# Cargador_RasPi3HAT_CamSlot_v1_0.net
KiCad netlist of a schematic drawn in EAGLE
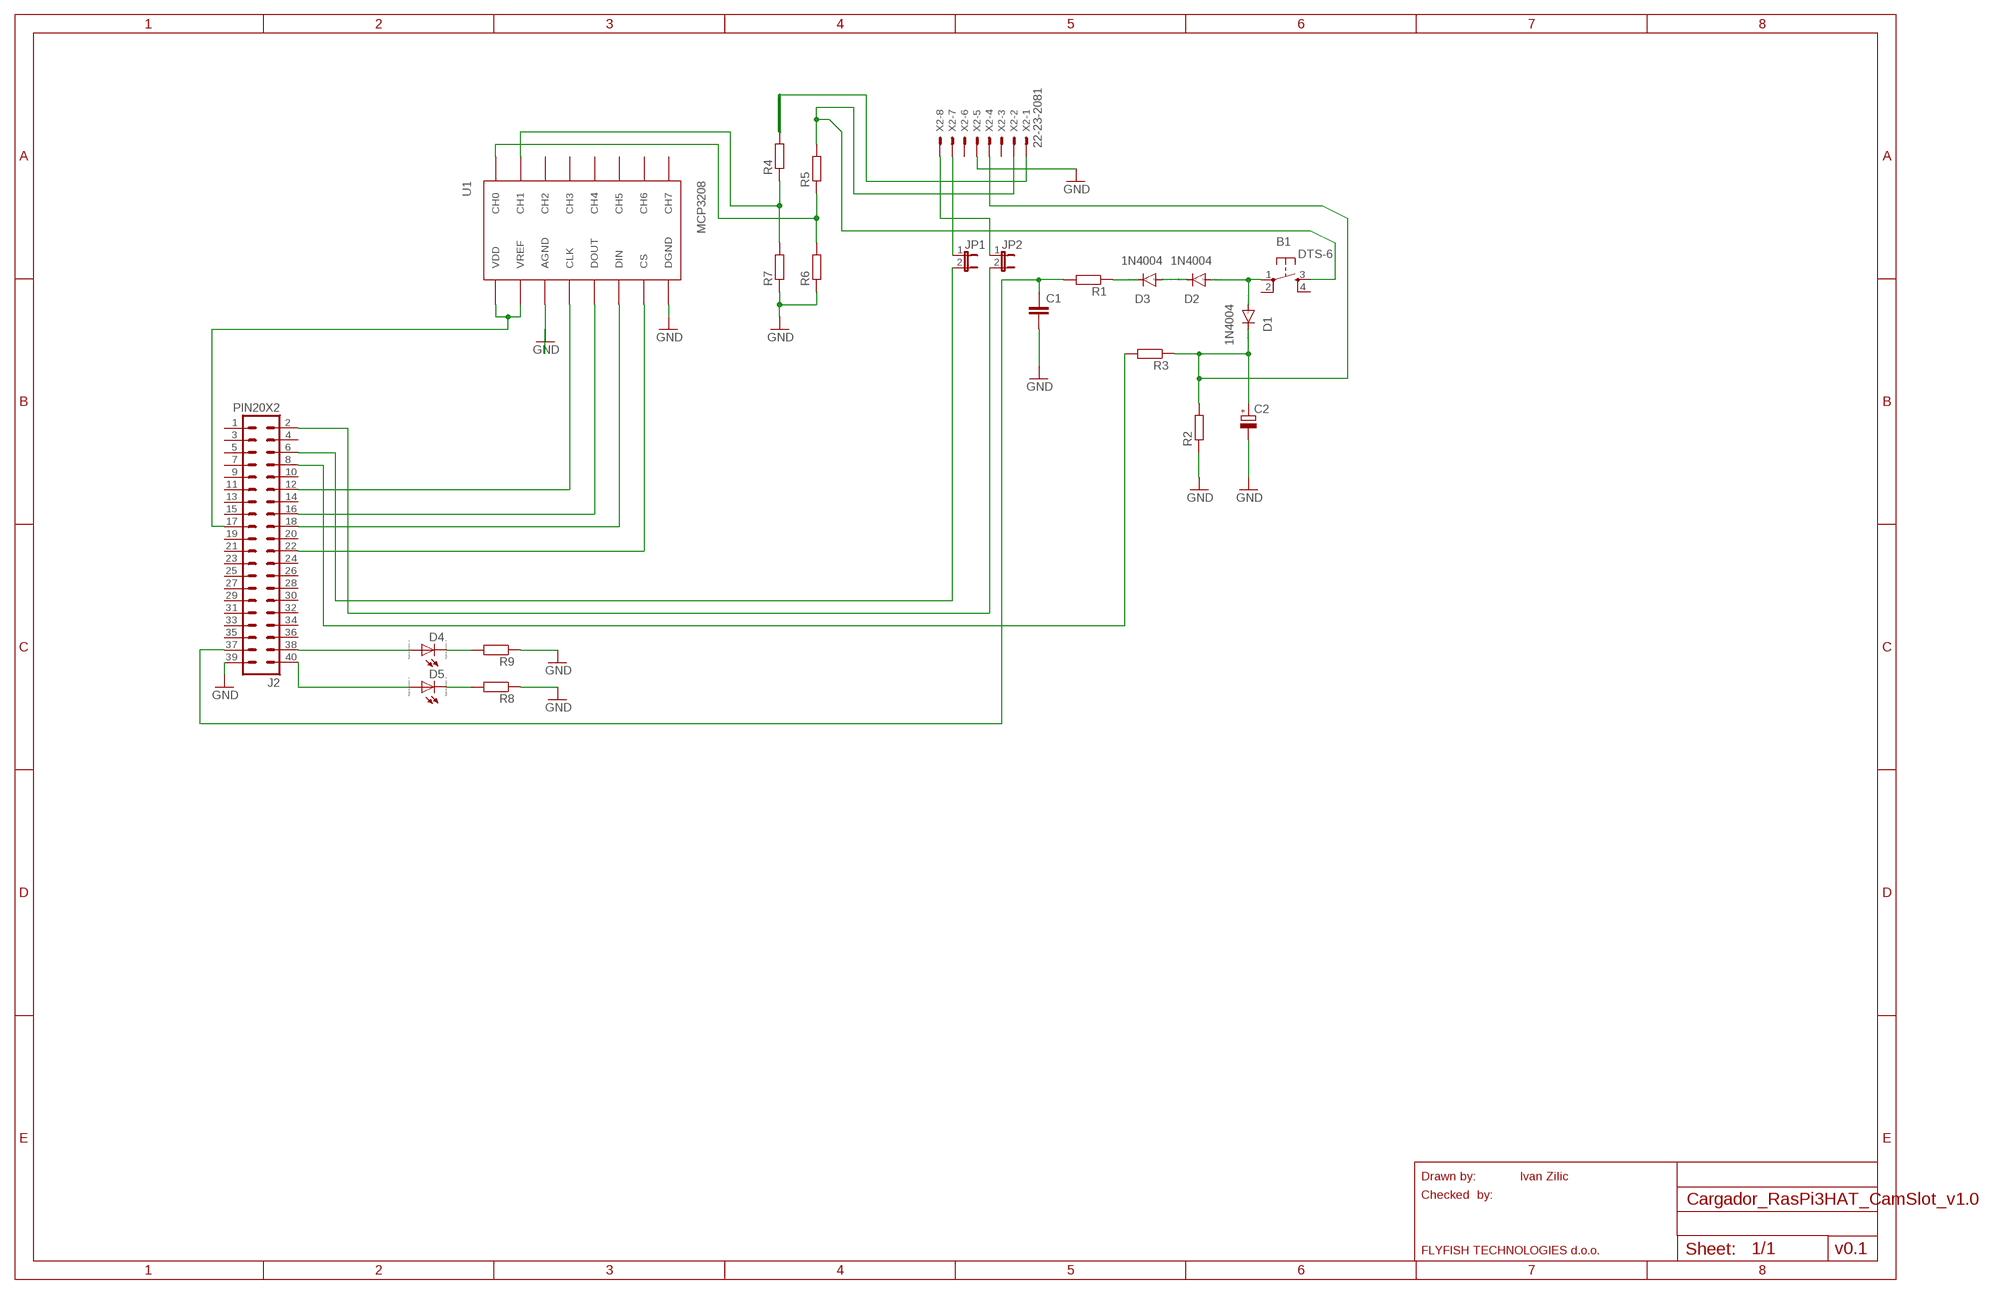
[diagram p0: schematic, sheet 1]

(export (version "E")
  (design (tool "Eeschema 10.0.6"))
  (components
    (comp (ref "B1")
      (value "DTS-6")
      (footprint "eagle-import:DTS-6")
      (libsource (lib "eagle-import") (part "DTS-6"))
    )
    (comp (ref "C1")
      (value "C2.5/2")
      (footprint "eagle-import:C2.5-2")
      (libsource (lib "eagle-import") (part "C2.5/2"))
    )
    (comp (ref "C2")
      (value "CPOL-EUE5-4")
      (footprint "eagle-import:E5-4")
      (libsource (lib "eagle-import") (part "CPOL-EUE5-4"))
    )
    (comp (ref "D1")
      (value "1N4004")
      (footprint "eagle-import:DO41-10")
      (libsource (lib "eagle-import") (part "1N4004"))
    )
    (comp (ref "D2")
      (value "1N4004")
      (footprint "eagle-import:DO41-10")
      (libsource (lib "eagle-import") (part "1N4004"))
    )
    (comp (ref "D3")
      (value "1N4004")
      (footprint "eagle-import:DO41-10")
      (libsource (lib "eagle-import") (part "1N4004"))
    )
    (comp (ref "D4")
      (value "LED_ELD260")
      (footprint "eagle-import:LED_LD260")
      (libsource (lib "eagle-import") (part "LED_ELD260"))
    )
    (comp (ref "D5")
      (value "LED_ELD260")
      (footprint "eagle-import:LED_LD260")
      (libsource (lib "eagle-import") (part "LED_ELD260"))
    )
    (comp (ref "J2")
      (value "PIN20X2")
      (footprint "eagle-import:PIN_20X2")
      (libsource (lib "eagle-import") (part "PIN20X2"))
    )
    (comp (ref "JP1")
      (value "JP1E")
      (footprint "eagle-import:JP1")
      (libsource (lib "eagle-import") (part "JP1E"))
    )
    (comp (ref "JP2")
      (value "JP1E")
      (footprint "eagle-import:JP1")
      (libsource (lib "eagle-import") (part "JP1E"))
    )
    (comp (ref "R1")
      (value "R-EU_0207/10")
      (footprint "eagle-import:0207_10")
      (libsource (lib "eagle-import") (part "R-EU_0207/10"))
    )
    (comp (ref "R2")
      (value "R-EU_0207/10")
      (footprint "eagle-import:0207_10")
      (libsource (lib "eagle-import") (part "R-EU_0207/10"))
    )
    (comp (ref "R3")
      (value "R-EU_0207/10")
      (footprint "eagle-import:0207_10")
      (libsource (lib "eagle-import") (part "R-EU_0207/10"))
    )
    (comp (ref "R4")
      (value "R-EU_0207/10")
      (footprint "eagle-import:0207_10")
      (libsource (lib "eagle-import") (part "R-EU_0207/10"))
    )
    (comp (ref "R5")
      (value "R-EU_0207/10")
      (footprint "eagle-import:0207_10")
      (libsource (lib "eagle-import") (part "R-EU_0207/10"))
    )
    (comp (ref "R6")
      (value "R-EU_0207/10")
      (footprint "eagle-import:0207_10")
      (libsource (lib "eagle-import") (part "R-EU_0207/10"))
    )
    (comp (ref "R7")
      (value "R-EU_0207/10")
      (footprint "eagle-import:0207_10")
      (libsource (lib "eagle-import") (part "R-EU_0207/10"))
    )
    (comp (ref "R8")
      (value "R-EU_0207/10")
      (footprint "eagle-import:0207_10")
      (libsource (lib "eagle-import") (part "R-EU_0207/10"))
    )
    (comp (ref "R9")
      (value "R-EU_0207/10")
      (footprint "eagle-import:0207_10")
      (libsource (lib "eagle-import") (part "R-EU_0207/10"))
    )
    (comp (ref "U1")
      (value "MCP3208")
      (footprint "eagle-import:DIL16")
      (libsource (lib "eagle-import") (part "MCP3208"))
    )
    (comp (ref "X2")
      (value "22-23-2081")
      (footprint "eagle-import:22-23-2081")
      (fields (field (name "MF") "MOLEX"))
      (libsource (lib "eagle-import") (part "22-23-2081"))
    )
  )
  (nets
    (net (code "1") (name "GND") (class "Default")
      (node (ref "C1") (pin "2") (pinfunction "2_2") (pintype "passive"))
      (node (ref "C2") (pin "-") (pinfunction "-_-") (pintype "passive"))
      (node (ref "J2") (pin "39") (pinfunction "39_39") (pintype "passive"))
      (node (ref "R2") (pin "1") (pinfunction "1_1") (pintype "passive"))
      (node (ref "R6") (pin "1") (pinfunction "1_1") (pintype "passive"))
      (node (ref "R7") (pin "1") (pinfunction "1_1") (pintype "passive"))
      (node (ref "R8") (pin "1") (pinfunction "1_1") (pintype "passive"))
      (node (ref "R9") (pin "1") (pinfunction "1_1") (pintype "passive"))
      (node (ref "U1") (pin "AGND") (pinfunction "AGND_AGND") (pintype "power_in"))
      (node (ref "U1") (pin "DGND") (pinfunction "DGND_DGND") (pintype "power_in"))
      (node (ref "X2") (pin "5") (pinfunction "S_5") (pintype "passive"))
    )
    (net (code "2") (name "Net-(B1-Pad1)") (class "Default")
      (node (ref "B1") (pin "1") (pinfunction "1_1") (pintype "passive"))
      (node (ref "D1") (pin "A") (pinfunction "A_A") (pintype "passive"))
      (node (ref "D2") (pin "A") (pinfunction "A_A") (pintype "passive"))
    )
    (net (code "3") (name "Net-(C1-Pad1)") (class "Default")
      (node (ref "C1") (pin "1") (pinfunction "1_1") (pintype "passive"))
      (node (ref "J2") (pin "37") (pinfunction "37_37") (pintype "passive"))
      (node (ref "R1") (pin "2") (pinfunction "2_2") (pintype "passive"))
    )
    (net (code "4") (name "Net-(D2-PadC)") (class "Default")
      (node (ref "D2") (pin "C") (pinfunction "C_C") (pintype "passive"))
      (node (ref "D3") (pin "A") (pinfunction "A_A") (pintype "passive"))
    )
    (net (code "5") (name "Net-(D3-PadC)") (class "Default")
      (node (ref "D3") (pin "C") (pinfunction "C_C") (pintype "passive"))
      (node (ref "R1") (pin "1") (pinfunction "1_1") (pintype "passive"))
    )
    (net (code "6") (name "Net-(D4-C)") (class "Default")
      (node (ref "D4") (pin "K") (pinfunction "C_K") (pintype "passive"))
      (node (ref "R9") (pin "2") (pinfunction "2_2") (pintype "passive"))
    )
    (net (code "7") (name "Net-(D4-PadA)") (class "Default")
      (node (ref "D4") (pin "A") (pinfunction "A_A") (pintype "passive"))
      (node (ref "J2") (pin "38") (pinfunction "38_38") (pintype "passive"))
    )
    (net (code "8") (name "Net-(D5-C)") (class "Default")
      (node (ref "D5") (pin "K") (pinfunction "C_K") (pintype "passive"))
      (node (ref "R8") (pin "2") (pinfunction "2_2") (pintype "passive"))
    )
    (net (code "9") (name "Net-(D5-PadA)") (class "Default")
      (node (ref "D5") (pin "A") (pinfunction "A_A") (pintype "passive"))
      (node (ref "J2") (pin "40") (pinfunction "40_40") (pintype "passive"))
    )
    (net (code "10") (name "Net-(J2-Pad2)") (class "Default")
      (node (ref "J2") (pin "2") (pinfunction "2_2") (pintype "passive"))
      (node (ref "JP2") (pin "2") (pinfunction "2_2") (pintype "passive"))
    )
    (net (code "11") (name "Net-(J2-Pad6)") (class "Default")
      (node (ref "J2") (pin "6") (pinfunction "6_6") (pintype "passive"))
      (node (ref "JP1") (pin "2") (pinfunction "2_2") (pintype "passive"))
    )
    (net (code "12") (name "Net-(J2-Pad8)") (class "Default")
      (node (ref "J2") (pin "8") (pinfunction "8_8") (pintype "passive"))
      (node (ref "R3") (pin "2") (pinfunction "2_2") (pintype "passive"))
    )
    (net (code "13") (name "Net-(J2-Pad12)") (class "Default")
      (node (ref "J2") (pin "12") (pinfunction "12_12") (pintype "passive"))
      (node (ref "U1") (pin "CLK") (pinfunction "CLK_CLK") (pintype "input"))
    )
    (net (code "14") (name "Net-(J2-Pad16)") (class "Default")
      (node (ref "J2") (pin "16") (pinfunction "16_16") (pintype "passive"))
      (node (ref "U1") (pin "DOUT") (pinfunction "DOUT_DOUT") (pintype "output"))
    )
    (net (code "15") (name "Net-(J2-Pad17)") (class "Default")
      (node (ref "J2") (pin "17") (pinfunction "17_17") (pintype "passive"))
      (node (ref "U1") (pin "VDD") (pinfunction "VDD_VDD") (pintype "power_in"))
      (node (ref "U1") (pin "VREF") (pinfunction "VREF_VREF") (pintype "input"))
    )
    (net (code "16") (name "Net-(J2-Pad18)") (class "Default")
      (node (ref "J2") (pin "18") (pinfunction "18_18") (pintype "passive"))
      (node (ref "U1") (pin "DIN") (pinfunction "DIN_DIN") (pintype "input"))
    )
    (net (code "17") (name "Net-(J2-Pad22)") (class "Default")
      (node (ref "J2") (pin "22") (pinfunction "22_22") (pintype "passive"))
      (node (ref "U1") (pin "CS") (pinfunction "CS_CS") (pintype "input"))
    )
    (net (code "18") (name "Net-(R4-Pad1)") (class "Default")
      (node (ref "R4") (pin "1") (pinfunction "1_1") (pintype "passive"))
      (node (ref "R7") (pin "2") (pinfunction "2_2") (pintype "passive"))
      (node (ref "U1") (pin "CH1") (pinfunction "CH1_CH1") (pintype "input"))
    )
    (net (code "19") (name "Net-(R5-Pad1)") (class "Default")
      (node (ref "R5") (pin "1") (pinfunction "1_1") (pintype "passive"))
      (node (ref "R6") (pin "2") (pinfunction "2_2") (pintype "passive"))
      (node (ref "U1") (pin "CH0") (pinfunction "CH0_CH0") (pintype "input"))
    )
    (net (code "20") (name "Net-(X2A-S)") (class "Default")
      (node (ref "R4") (pin "2") (pinfunction "2_2") (pintype "passive"))
      (node (ref "X2") (pin "1") (pinfunction "S_1") (pintype "passive"))
    )
    (net (code "21") (name "Net-(X2B-S)") (class "Default")
      (node (ref "B1") (pin "3") (pinfunction "3_3") (pintype "passive"))
      (node (ref "R5") (pin "2") (pinfunction "2_2") (pintype "passive"))
      (node (ref "X2") (pin "2") (pinfunction "S_2") (pintype "passive"))
    )
    (net (code "22") (name "Net-(X2D-S)") (class "Default")
      (node (ref "C2") (pin "+") (pinfunction "+_+") (pintype "passive"))
      (node (ref "D1") (pin "C") (pinfunction "C_C") (pintype "passive"))
      (node (ref "R2") (pin "2") (pinfunction "2_2") (pintype "passive"))
      (node (ref "R3") (pin "1") (pinfunction "1_1") (pintype "passive"))
      (node (ref "X2") (pin "4") (pinfunction "S_4") (pintype "passive"))
    )
    (net (code "23") (name "Net-(X2G-S)") (class "Default")
      (node (ref "JP1") (pin "1") (pinfunction "1_1") (pintype "passive"))
      (node (ref "X2") (pin "7") (pinfunction "S_7") (pintype "passive"))
    )
    (net (code "24") (name "Net-(X2H-S)") (class "Default")
      (node (ref "JP2") (pin "1") (pinfunction "1_1") (pintype "passive"))
      (node (ref "X2") (pin "8") (pinfunction "S_8") (pintype "passive"))
    )
    (net (code "25") (name "unconnected-(B1-Pad2)") (class "Default")
      (node (ref "B1") (pin "2") (pinfunction "2_2") (pintype "passive"))
    )
    (net (code "26") (name "unconnected-(B1-Pad4)") (class "Default")
      (node (ref "B1") (pin "4") (pinfunction "4_4") (pintype "passive"))
    )
    (net (code "27") (name "unconnected-(J2-Pad1)") (class "Default")
      (node (ref "J2") (pin "1") (pinfunction "1_1") (pintype "passive"))
    )
    (net (code "28") (name "unconnected-(J2-Pad3)") (class "Default")
      (node (ref "J2") (pin "3") (pinfunction "3_3") (pintype "passive"))
    )
    (net (code "29") (name "unconnected-(J2-Pad4)") (class "Default")
      (node (ref "J2") (pin "4") (pinfunction "4_4") (pintype "passive"))
    )
    (net (code "30") (name "unconnected-(J2-Pad5)") (class "Default")
      (node (ref "J2") (pin "5") (pinfunction "5_5") (pintype "passive"))
    )
    (net (code "31") (name "unconnected-(J2-Pad7)") (class "Default")
      (node (ref "J2") (pin "7") (pinfunction "7_7") (pintype "passive"))
    )
    (net (code "32") (name "unconnected-(J2-Pad9)") (class "Default")
      (node (ref "J2") (pin "9") (pinfunction "9_9") (pintype "passive"))
    )
    (net (code "33") (name "unconnected-(J2-Pad10)") (class "Default")
      (node (ref "J2") (pin "10") (pinfunction "10_10") (pintype "passive"))
    )
    (net (code "34") (name "unconnected-(J2-Pad11)") (class "Default")
      (node (ref "J2") (pin "11") (pinfunction "11_11") (pintype "passive"))
    )
    (net (code "35") (name "unconnected-(J2-Pad13)") (class "Default")
      (node (ref "J2") (pin "13") (pinfunction "13_13") (pintype "passive"))
    )
    (net (code "36") (name "unconnected-(J2-Pad14)") (class "Default")
      (node (ref "J2") (pin "14") (pinfunction "14_14") (pintype "passive"))
    )
    (net (code "37") (name "unconnected-(J2-Pad15)") (class "Default")
      (node (ref "J2") (pin "15") (pinfunction "15_15") (pintype "passive"))
    )
    (net (code "38") (name "unconnected-(J2-Pad19)") (class "Default")
      (node (ref "J2") (pin "19") (pinfunction "19_19") (pintype "passive"))
    )
    (net (code "39") (name "unconnected-(J2-Pad20)") (class "Default")
      (node (ref "J2") (pin "20") (pinfunction "20_20") (pintype "passive"))
    )
    (net (code "40") (name "unconnected-(J2-Pad21)") (class "Default")
      (node (ref "J2") (pin "21") (pinfunction "21_21") (pintype "passive"))
    )
    (net (code "41") (name "unconnected-(J2-Pad23)") (class "Default")
      (node (ref "J2") (pin "23") (pinfunction "23_23") (pintype "passive"))
    )
    (net (code "42") (name "unconnected-(J2-Pad24)") (class "Default")
      (node (ref "J2") (pin "24") (pinfunction "24_24") (pintype "passive"))
    )
    (net (code "43") (name "unconnected-(J2-Pad25)") (class "Default")
      (node (ref "J2") (pin "25") (pinfunction "25_25") (pintype "passive"))
    )
    (net (code "44") (name "unconnected-(J2-Pad26)") (class "Default")
      (node (ref "J2") (pin "26") (pinfunction "26_26") (pintype "passive"))
    )
    (net (code "45") (name "unconnected-(J2-Pad27)") (class "Default")
      (node (ref "J2") (pin "27") (pinfunction "27_27") (pintype "passive"))
    )
    (net (code "46") (name "unconnected-(J2-Pad28)") (class "Default")
      (node (ref "J2") (pin "28") (pinfunction "28_28") (pintype "passive"))
    )
    (net (code "47") (name "unconnected-(J2-Pad29)") (class "Default")
      (node (ref "J2") (pin "29") (pinfunction "29_29") (pintype "passive"))
    )
    (net (code "48") (name "unconnected-(J2-Pad30)") (class "Default")
      (node (ref "J2") (pin "30") (pinfunction "30_30") (pintype "passive"))
    )
    (net (code "49") (name "unconnected-(J2-Pad31)") (class "Default")
      (node (ref "J2") (pin "31") (pinfunction "31_31") (pintype "passive"))
    )
    (net (code "50") (name "unconnected-(J2-Pad32)") (class "Default")
      (node (ref "J2") (pin "32") (pinfunction "32_32") (pintype "passive"))
    )
    (net (code "51") (name "unconnected-(J2-Pad33)") (class "Default")
      (node (ref "J2") (pin "33") (pinfunction "33_33") (pintype "passive"))
    )
    (net (code "52") (name "unconnected-(J2-Pad34)") (class "Default")
      (node (ref "J2") (pin "34") (pinfunction "34_34") (pintype "passive"))
    )
    (net (code "53") (name "unconnected-(J2-Pad35)") (class "Default")
      (node (ref "J2") (pin "35") (pinfunction "35_35") (pintype "passive"))
    )
    (net (code "54") (name "unconnected-(J2-Pad36)") (class "Default")
      (node (ref "J2") (pin "36") (pinfunction "36_36") (pintype "passive"))
    )
    (net (code "55") (name "unconnected-(U1-PadCH2)") (class "Default")
      (node (ref "U1") (pin "CH2") (pinfunction "CH2_CH2") (pintype "input"))
    )
    (net (code "56") (name "unconnected-(U1-PadCH3)") (class "Default")
      (node (ref "U1") (pin "CH3") (pinfunction "CH3_CH3") (pintype "input"))
    )
    (net (code "57") (name "unconnected-(U1-PadCH4)") (class "Default")
      (node (ref "U1") (pin "CH4") (pinfunction "CH4_CH4") (pintype "input"))
    )
    (net (code "58") (name "unconnected-(U1-PadCH5)") (class "Default")
      (node (ref "U1") (pin "CH5") (pinfunction "CH5_CH5") (pintype "input"))
    )
    (net (code "59") (name "unconnected-(U1-PadCH6)") (class "Default")
      (node (ref "U1") (pin "CH6") (pinfunction "CH6_CH6") (pintype "input"))
    )
    (net (code "60") (name "unconnected-(U1-PadCH7)") (class "Default")
      (node (ref "U1") (pin "CH7") (pinfunction "CH7_CH7") (pintype "input"))
    )
    (net (code "61") (name "unconnected-(X2C-S-Pad3)") (class "Default")
      (node (ref "X2") (pin "3") (pinfunction "S_3") (pintype "passive"))
    )
    (net (code "62") (name "unconnected-(X2F-S-Pad6)") (class "Default")
      (node (ref "X2") (pin "6") (pinfunction "S_6") (pintype "passive"))
    )
  )
)
